# house_sch.net
KiCad netlist of a schematic drawn in Altium Designer
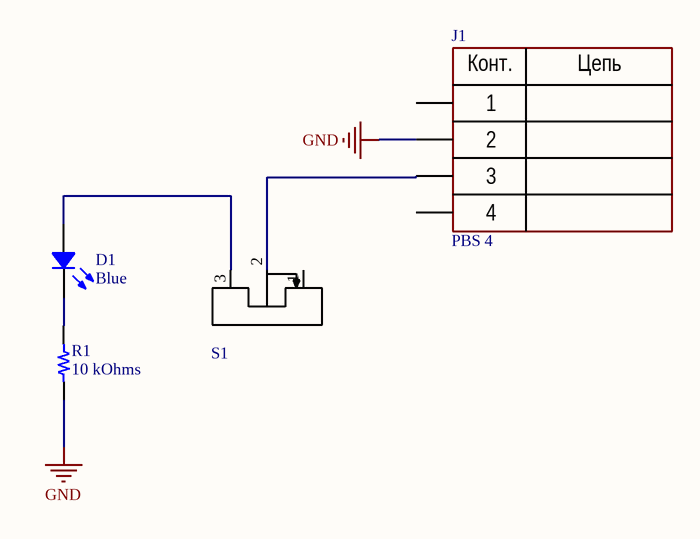
[diagram p0: house_sch.SchDoc]

(export (version "E")
  (design (tool "Eeschema 10.0.6"))
  (components
    (comp (ref "*") (value "S1") (footprint "switcher") (libsource (lib "liba") (part "switcher")))
    (comp (ref "D1")
      (value "Blue")
      (footprint "LED 1206_3216 BLUE")
      (description "LED BLUE CLEAR SMD")
      (fields
        (field (name "PART NUMBER") "SML-LXLC1206USBCTR")
        (field (name "MANUFACTURER") "Lumex Opto/Components Inc.")
      )
      (libsource (lib "Celestial Altium Library - altium_library") (part "LED"))
    )
    (comp (ref "J1") (value "PBS 4") (footprint "PBS-4 CUT") (libsource (lib "liba") (part "PBS 4")))
    (comp (ref "R1")
      (value "10 kOhms")
      (footprint "RES 0603_1608")
      (description "RES 10K OHM 0.1% 1/16W 0603")
      (fields
        (field (name "PART NUMBER") "RNCS0603BKE10K0")
        (field (name "MANUFACTURER") "Stackpole Electronics Inc")
      )
      (libsource (lib "Celestial Altium Library - altium_library") (part "Resistor"))
    )
  )
  (nets
    (net (code "1") (name "GND") (class "Default")
      (node (ref "J1") (pin "2") (pinfunction "2_2") (pintype "passive"))
      (node (ref "R1") (pin "1") (pinfunction "1_1") (pintype "passive"))
    )
    (net (code "2") (name "Net-(*-Pad2)") (class "Default")
      (node (ref "*") (pin "2") (pinfunction "2_2") (pintype "passive"))
      (node (ref "J1") (pin "3") (pinfunction "3_3") (pintype "passive"))
    )
    (net (code "3") (name "Net-(*-Pad3)") (class "Default")
      (node (ref "*") (pin "3") (pinfunction "3_3") (pintype "passive"))
      (node (ref "D1") (pin "1") (pinfunction "1_1") (pintype "passive"))
    )
    (net (code "4") (name "Net-(D1-Pad2)") (class "Default")
      (node (ref "D1") (pin "2") (pinfunction "2_2") (pintype "passive"))
      (node (ref "R1") (pin "2") (pinfunction "2_2") (pintype "passive"))
    )
    (net (code "5") (name "unconnected-(*-Pad1)") (class "Default")
      (node (ref "*") (pin "1") (pinfunction "1_1") (pintype "passive"))
    )
    (net (code "6") (name "unconnected-(J1-Pad1)") (class "Default")
      (node (ref "J1") (pin "1") (pinfunction "1_1") (pintype "passive"))
    )
    (net (code "7") (name "unconnected-(J1-Pad4)") (class "Default")
      (node (ref "J1") (pin "4") (pinfunction "4_4") (pintype "passive"))
    )
  )
)
